# accra_a0_B.net
KiCad netlist of a schematic drawn in EAGLE
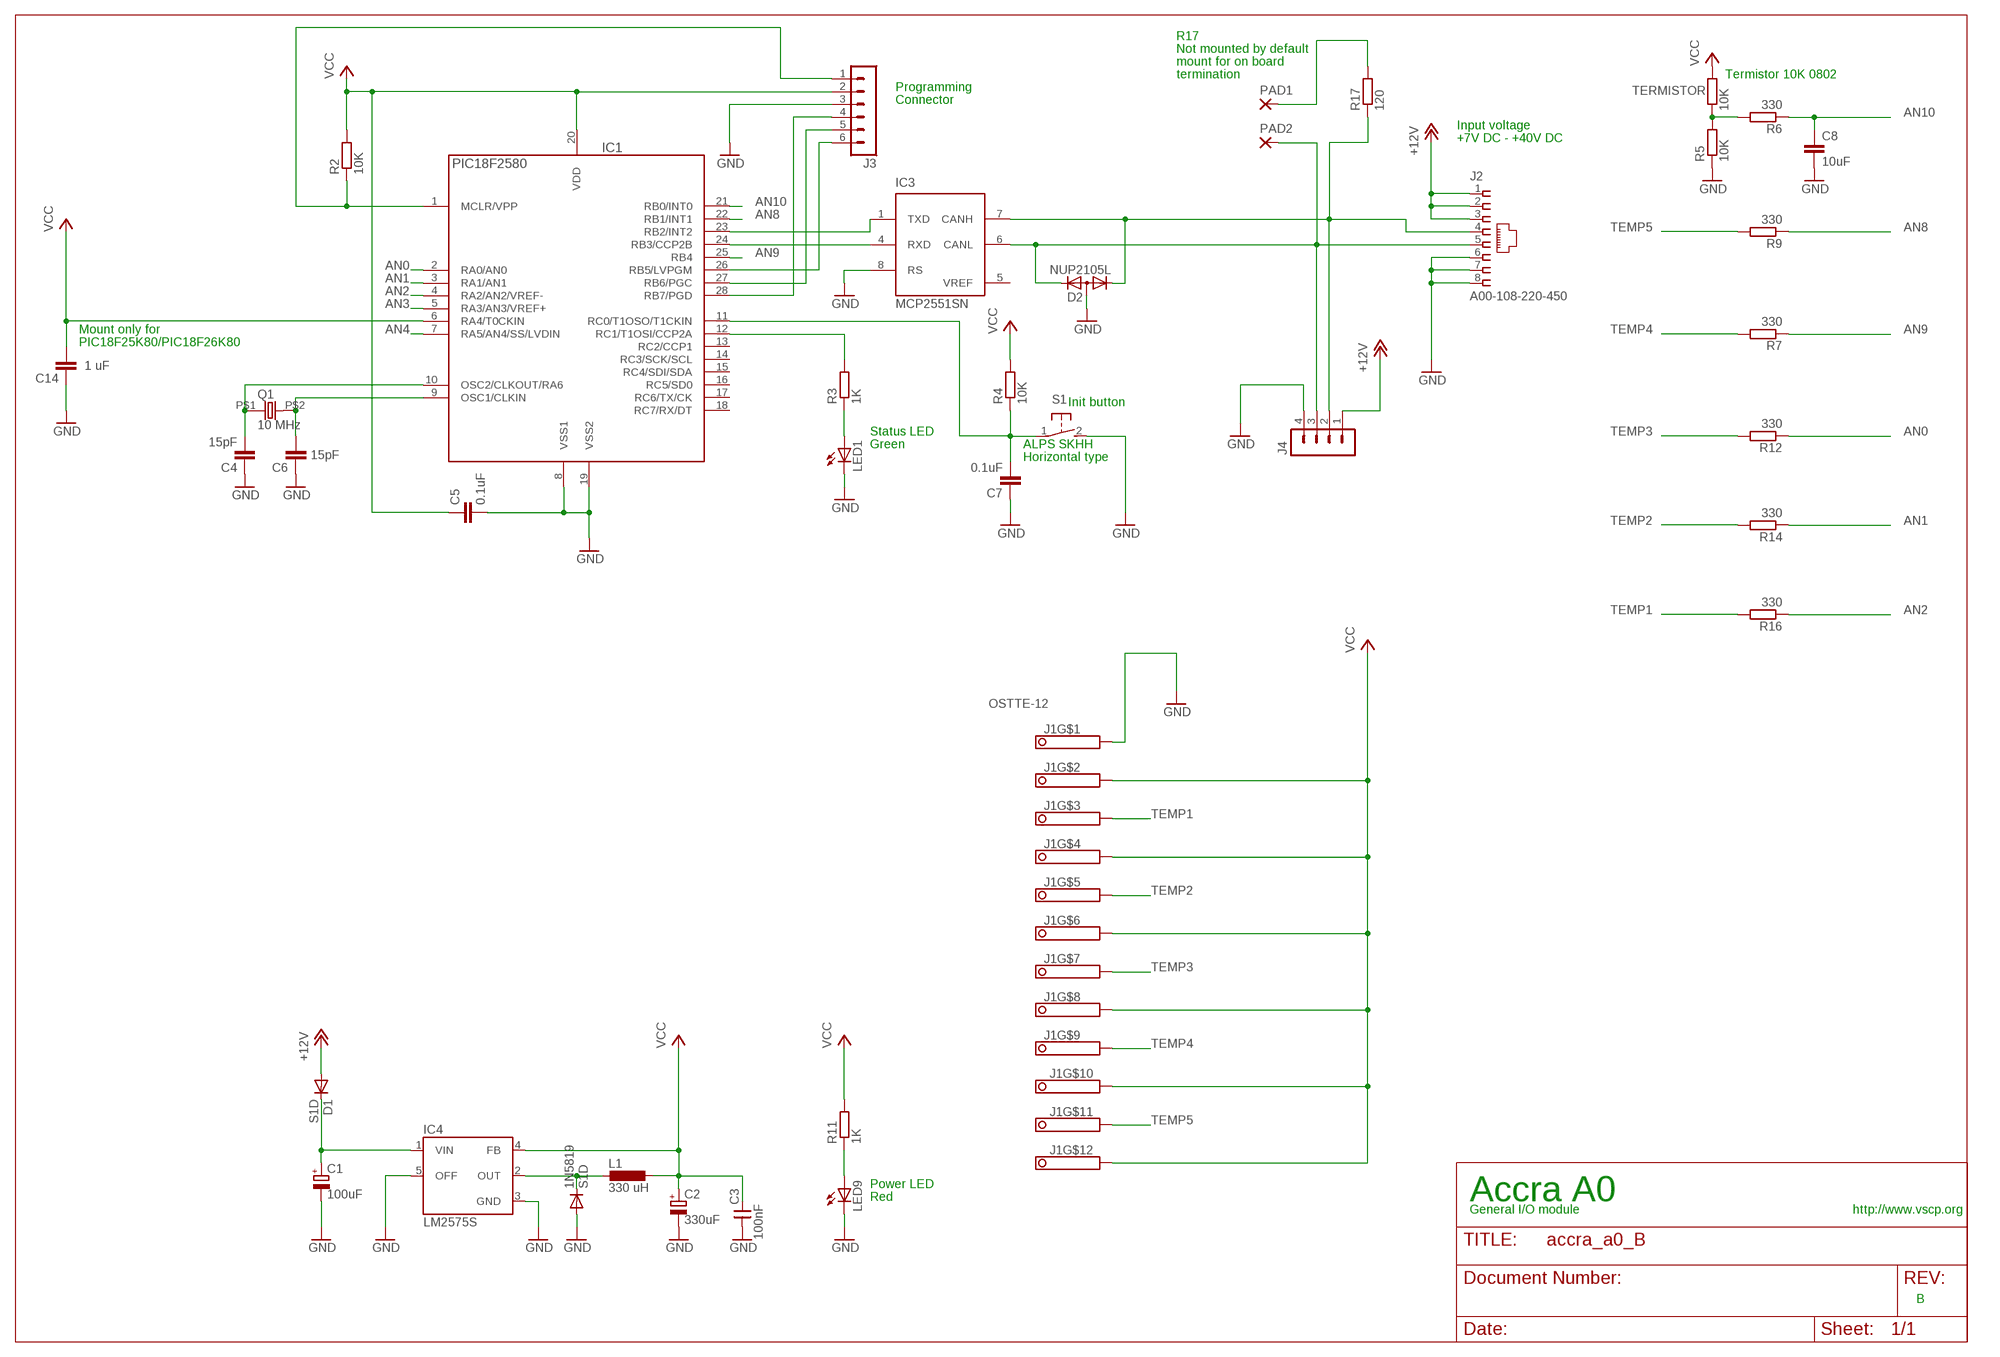
[diagram p0: schematic, sheet 1]

(export (version "E")
  (design (tool "Eeschema 10.0.6"))
  (components
    (comp (ref "1N5819")
      (value "S1D")
      (footprint "eagle-import:SOD123")
      (libsource (lib "eagle-import") (part "DIODE-SOD123"))
    )
    (comp (ref "C1")
      (value "100uF")
      (footprint "eagle-import:PANASONIC_D")
      (libsource (lib "eagle-import") (part "CPOL-EUD"))
    )
    (comp (ref "C2")
      (value "330uF")
      (footprint "eagle-import:PANASONIC_D")
      (libsource (lib "eagle-import") (part "CPOL-EUD"))
    )
    (comp (ref "C3")
      (value "100nF")
      (footprint "eagle-import:0805")
      (libsource (lib "eagle-import") (part "CNP-0805"))
    )
    (comp (ref "C4")
      (value "15pF")
      (footprint "eagle-import:C0805")
      (libsource (lib "eagle-import") (part "C-EUC0805"))
    )
    (comp (ref "C5")
      (value "0.1uF")
      (footprint "eagle-import:C0805")
      (libsource (lib "eagle-import") (part "C-EUC0805"))
    )
    (comp (ref "C6")
      (value "15pF")
      (footprint "eagle-import:C0805")
      (libsource (lib "eagle-import") (part "C-EUC0805"))
    )
    (comp (ref "C7")
      (value "0.1uF")
      (footprint "eagle-import:C0805")
      (libsource (lib "eagle-import") (part "C-EUC0805"))
    )
    (comp (ref "C8")
      (value "10uF")
      (footprint "eagle-import:C0805")
      (libsource (lib "eagle-import") (part "C-EUC0805"))
    )
    (comp (ref "C14")
      (value "1 uF")
      (footprint "eagle-import:C0805")
      (libsource (lib "eagle-import") (part "C-EUC0805"))
    )
    (comp (ref "D1")
      (value "S1D")
      (footprint "eagle-import:SOD123")
      (libsource (lib "eagle-import") (part "DIODE-SOD123"))
    )
    (comp (ref "D2")
      (value "NUP2105L")
      (footprint "eagle-import:SOT23")
      (libsource (lib "eagle-import") (part "DIODE-2CA|ACSOT23"))
    )
    (comp (ref "IC1")
      (value "PIC18F2580")
      (footprint "eagle-import:SO28")
      (libsource (lib "eagle-import") (part "PIC18F252-?I/SOL"))
    )
    (comp (ref "IC3")
      (value "MCP2551SN")
      (footprint "eagle-import:SO-08")
      (libsource (lib "eagle-import") (part "MCP2551SN"))
    )
    (comp (ref "IC4")
      (value "LM2575S")
      (footprint "eagle-import:TO263-5")
      (libsource (lib "eagle-import") (part "LM2575S"))
    )
    (comp (ref "J1")
      (value "OSTTE-12")
      (footprint "eagle-import:PINHEAD-12")
      (libsource (lib "eagle-import") (part "OSTTE-12"))
    )
    (comp (ref "J2")
      (value "A00-108-220-450")
      (footprint "eagle-import:RJ-45")
      (libsource (lib "eagle-import") (part "A00-108-220-450"))
    )
    (comp (ref "J3")
      (value "MA06-1")
      (footprint "eagle-import:MA06-1")
      (libsource (lib "eagle-import") (part "MA06-1"))
    )
    (comp (ref "J4")
      (value "MA04-1")
      (footprint "eagle-import:MA04-1")
      (libsource (lib "eagle-import") (part "MA04-1"))
    )
    (comp (ref "L1")
      (value "330 uH")
      (footprint "eagle-import:DO3316P")
      (libsource (lib "eagle-import") (part "DO3316P"))
    )
    (comp (ref "LED1")
      (value "LEDCHIP-LED0805")
      (footprint "eagle-import:CHIP-LED0805")
      (libsource (lib "eagle-import") (part "LEDCHIP-LED0805"))
    )
    (comp (ref "LED9")
      (value "LEDCHIP-LED0805")
      (footprint "eagle-import:CHIP-LED0805")
      (libsource (lib "eagle-import") (part "LEDCHIP-LED0805"))
    )
    (comp (ref "PAD1")
      (value "1,6/0,8")
      (footprint "eagle-import:1,6_0,8")
      (libsource (lib "eagle-import") (part "1,6/0,8"))
    )
    (comp (ref "PAD2")
      (value "1,6/0,8")
      (footprint "eagle-import:1,6_0,8")
      (libsource (lib "eagle-import") (part "1,6/0,8"))
    )
    (comp (ref "Q1")
      (value "10 MHz")
      (footprint "eagle-import:9C")
      (libsource (lib "eagle-import") (part "HC-49S"))
    )
    (comp (ref "R2")
      (value "10K")
      (footprint "eagle-import:R0805")
      (libsource (lib "eagle-import") (part "R-EU_R0805"))
    )
    (comp (ref "R3")
      (value "1K")
      (footprint "eagle-import:R0805")
      (libsource (lib "eagle-import") (part "R-EU_R0805"))
    )
    (comp (ref "R4")
      (value "10K")
      (footprint "eagle-import:R0805")
      (libsource (lib "eagle-import") (part "R-EU_R0805"))
    )
    (comp (ref "R5")
      (value "10K")
      (footprint "eagle-import:R0805")
      (libsource (lib "eagle-import") (part "R-EU_R0805"))
    )
    (comp (ref "R6")
      (value "330")
      (footprint "eagle-import:R0805")
      (libsource (lib "eagle-import") (part "R-EU_R0805"))
    )
    (comp (ref "R7")
      (value "330")
      (footprint "eagle-import:R0805")
      (libsource (lib "eagle-import") (part "R-EU_R0805"))
    )
    (comp (ref "R9")
      (value "330")
      (footprint "eagle-import:R0805")
      (libsource (lib "eagle-import") (part "R-EU_R0805"))
    )
    (comp (ref "R11")
      (value "1K")
      (footprint "eagle-import:R0805")
      (libsource (lib "eagle-import") (part "R-EU_R0805"))
    )
    (comp (ref "R12")
      (value "330")
      (footprint "eagle-import:R0805")
      (libsource (lib "eagle-import") (part "R-EU_R0805"))
    )
    (comp (ref "R14")
      (value "330")
      (footprint "eagle-import:R0805")
      (libsource (lib "eagle-import") (part "R-EU_R0805"))
    )
    (comp (ref "R16")
      (value "330")
      (footprint "eagle-import:R0805")
      (libsource (lib "eagle-import") (part "R-EU_R0805"))
    )
    (comp (ref "R17")
      (value "120")
      (footprint "eagle-import:R0805")
      (libsource (lib "eagle-import") (part "R-EU_R0805"))
    )
    (comp (ref "S1")
      (value "31-XX")
      (footprint "eagle-import:B3F-31XX")
      (fields (field (name "MPN") "B3F-3100"))
      (libsource (lib "eagle-import") (part "31-XX"))
    )
    (comp (ref "TERMISTOR")
      (value "10K")
      (footprint "eagle-import:R0805")
      (libsource (lib "eagle-import") (part "R-EU_R0805"))
    )
  )
  (nets
    (net (code "1") (name "+12V") (class "Default")
      (node (ref "D1") (pin "A") (pinfunction "A_A") (pintype "passive"))
      (node (ref "J2") (pin "1") (pinfunction "1_1") (pintype "passive"))
      (node (ref "J2") (pin "2") (pinfunction "2_2") (pintype "passive"))
      (node (ref "J2") (pin "3") (pinfunction "3_3") (pintype "passive"))
      (node (ref "J4") (pin "1") (pinfunction "1_1") (pintype "passive"))
    )
    (net (code "2") (name "/AN0") (class "Default")
      (node (ref "IC1") (pin "2") (pinfunction "RA0/AN0_2") (pintype "bidirectional"))
      (node (ref "R12") (pin "1") (pinfunction "1_1") (pintype "passive"))
    )
    (net (code "3") (name "/AN1") (class "Default")
      (node (ref "IC1") (pin "3") (pinfunction "RA1/AN1_3") (pintype "bidirectional"))
      (node (ref "R14") (pin "1") (pinfunction "1_1") (pintype "passive"))
    )
    (net (code "4") (name "/AN2") (class "Default")
      (node (ref "IC1") (pin "4") (pinfunction "RA2/AN2/VREF-_4") (pintype "bidirectional"))
      (node (ref "R16") (pin "1") (pinfunction "1_1") (pintype "passive"))
    )
    (net (code "5") (name "/AN3") (class "Default")
      (node (ref "IC1") (pin "5") (pinfunction "RA3/AN3/VREF+_5") (pintype "bidirectional"))
    )
    (net (code "6") (name "/AN4") (class "Default")
      (node (ref "IC1") (pin "7") (pinfunction "RA5/AN4/SS/LVDIN_7") (pintype "bidirectional"))
    )
    (net (code "7") (name "/AN8") (class "Default")
      (node (ref "IC1") (pin "22") (pinfunction "RB1/INT1_22") (pintype "bidirectional"))
      (node (ref "R9") (pin "1") (pinfunction "1_1") (pintype "passive"))
    )
    (net (code "8") (name "/AN9") (class "Default")
      (node (ref "IC1") (pin "25") (pinfunction "RB4_25") (pintype "bidirectional"))
      (node (ref "R7") (pin "1") (pinfunction "1_1") (pintype "passive"))
    )
    (net (code "9") (name "/AN10") (class "Default")
      (node (ref "C8") (pin "1") (pinfunction "1_1") (pintype "passive"))
      (node (ref "IC1") (pin "21") (pinfunction "RB0/INT0_21") (pintype "bidirectional"))
      (node (ref "R6") (pin "1") (pinfunction "1_1") (pintype "passive"))
    )
    (net (code "10") (name "/TEMP1") (class "Default")
      (node (ref "J1") (pin "3") (pinfunction "K_3") (pintype "passive"))
      (node (ref "R16") (pin "2") (pinfunction "2_2") (pintype "passive"))
    )
    (net (code "11") (name "/TEMP2") (class "Default")
      (node (ref "J1") (pin "5") (pinfunction "K_5") (pintype "passive"))
      (node (ref "R14") (pin "2") (pinfunction "2_2") (pintype "passive"))
    )
    (net (code "12") (name "/TEMP3") (class "Default")
      (node (ref "J1") (pin "7") (pinfunction "K_7") (pintype "passive"))
      (node (ref "R12") (pin "2") (pinfunction "2_2") (pintype "passive"))
    )
    (net (code "13") (name "/TEMP4") (class "Default")
      (node (ref "J1") (pin "9") (pinfunction "K_9") (pintype "passive"))
      (node (ref "R7") (pin "2") (pinfunction "2_2") (pintype "passive"))
    )
    (net (code "14") (name "/TEMP5") (class "Default")
      (node (ref "J1") (pin "11") (pinfunction "K_11") (pintype "passive"))
      (node (ref "R9") (pin "2") (pinfunction "2_2") (pintype "passive"))
    )
    (net (code "15") (name "/VREF") (class "Default")
      (node (ref "IC3") (pin "5") (pinfunction "VREF_5") (pintype "power_in"))
    )
    (net (code "16") (name "GND") (class "Default")
      (node (ref "1N5819") (pin "A") (pinfunction "A_A") (pintype "passive"))
      (node (ref "C1") (pin "-") (pinfunction "-_-") (pintype "passive"))
      (node (ref "C14") (pin "1") (pinfunction "1_1") (pintype "passive"))
      (node (ref "C2") (pin "-") (pinfunction "-_-") (pintype "passive"))
      (node (ref "C3") (pin "1") (pinfunction "1_1") (pintype "passive"))
      (node (ref "C4") (pin "1") (pinfunction "1_1") (pintype "passive"))
      (node (ref "C5") (pin "2") (pinfunction "2_2") (pintype "passive"))
      (node (ref "C6") (pin "1") (pinfunction "1_1") (pintype "passive"))
      (node (ref "C7") (pin "1") (pinfunction "1_1") (pintype "passive"))
      (node (ref "C8") (pin "2") (pinfunction "2_2") (pintype "passive"))
      (node (ref "D2") (pin "3") (pinfunction "A_3") (pintype "passive"))
      (node (ref "IC1") (pin "19") (pinfunction "VSS2_19") (pintype "power_in"))
      (node (ref "IC1") (pin "8") (pinfunction "VSS1_8") (pintype "power_in"))
      (node (ref "IC3") (pin "8") (pinfunction "RS_8") (pintype "input"))
      (node (ref "IC4") (pin "3") (pinfunction "GND_3") (pintype "power_in"))
      (node (ref "IC4") (pin "5") (pinfunction "OFF_5") (pintype "input"))
      (node (ref "J1") (pin "1") (pinfunction "K_1") (pintype "passive"))
      (node (ref "J2") (pin "6") (pinfunction "6_6") (pintype "passive"))
      (node (ref "J2") (pin "7") (pinfunction "7_7") (pintype "passive"))
      (node (ref "J2") (pin "8") (pinfunction "8_8") (pintype "passive"))
      (node (ref "J3") (pin "3") (pinfunction "3_3") (pintype "passive"))
      (node (ref "J4") (pin "4") (pinfunction "4_4") (pintype "passive"))
      (node (ref "LED1") (pin "C") (pinfunction "C_C") (pintype "passive"))
      (node (ref "LED9") (pin "C") (pinfunction "C_C") (pintype "passive"))
      (node (ref "R5") (pin "1") (pinfunction "1_1") (pintype "passive"))
      (node (ref "S1") (pin "2") (pinfunction "S_2") (pintype "passive"))
    )
    (net (code "17") (name "Net-(D2-K1)") (class "Default")
      (node (ref "D2") (pin "1") (pinfunction "K1_1") (pintype "passive"))
      (node (ref "IC3") (pin "7") (pinfunction "CANH_7") (pintype "bidirectional"))
      (node (ref "J2") (pin "4") (pinfunction "4_4") (pintype "passive"))
      (node (ref "J4") (pin "2") (pinfunction "2_2") (pintype "passive"))
      (node (ref "R17") (pin "1") (pinfunction "1_1") (pintype "passive"))
    )
    (net (code "18") (name "Net-(D2-K2)") (class "Default")
      (node (ref "D2") (pin "2") (pinfunction "K2_2") (pintype "passive"))
      (node (ref "IC3") (pin "6") (pinfunction "CANL_6") (pintype "bidirectional"))
      (node (ref "J2") (pin "5") (pinfunction "5_5") (pintype "passive"))
      (node (ref "J4") (pin "3") (pinfunction "3_3") (pintype "passive"))
      (node (ref "PAD2") (pin "1") (pinfunction "P_1") (pintype "passive"))
    )
    (net (code "19") (name "Net-(IC1-MCLR{slash}VPP)") (class "Default")
      (node (ref "IC1") (pin "1") (pinfunction "MCLR/VPP_1") (pintype "input"))
      (node (ref "J3") (pin "1") (pinfunction "1_1") (pintype "passive"))
      (node (ref "R2") (pin "1") (pinfunction "1_1") (pintype "passive"))
    )
    (net (code "20") (name "Net-(IC1-OSC1{slash}CLKIN)") (class "Default")
      (node (ref "C6") (pin "2") (pinfunction "2_2") (pintype "passive"))
      (node (ref "IC1") (pin "9") (pinfunction "OSC1/CLKIN_9") (pintype "input"))
      (node (ref "Q1") (pin "P$2") (pinfunction "2_P$2") (pintype "passive"))
    )
    (net (code "21") (name "Net-(IC1-OSC2{slash}CLKOUT{slash}RA6)") (class "Default")
      (node (ref "C4") (pin "2") (pinfunction "2_2") (pintype "passive"))
      (node (ref "IC1") (pin "10") (pinfunction "OSC2/CLKOUT/RA6_10") (pintype "output"))
      (node (ref "Q1") (pin "P$1") (pinfunction "1_P$1") (pintype "passive"))
    )
    (net (code "22") (name "Net-(IC1-RB2{slash}INT2)") (class "Default")
      (node (ref "IC1") (pin "23") (pinfunction "RB2/INT2_23") (pintype "bidirectional"))
      (node (ref "IC3") (pin "1") (pinfunction "TXD_1") (pintype "input"))
    )
    (net (code "23") (name "Net-(IC1-RB3{slash}CCP2B)") (class "Default")
      (node (ref "IC1") (pin "24") (pinfunction "RB3/CCP2B_24") (pintype "bidirectional"))
      (node (ref "IC3") (pin "4") (pinfunction "RXD_4") (pintype "output"))
    )
    (net (code "24") (name "Net-(IC1-RB5{slash}LVPGM)") (class "Default")
      (node (ref "IC1") (pin "26") (pinfunction "RB5/LVPGM_26") (pintype "bidirectional"))
      (node (ref "J3") (pin "6") (pinfunction "6_6") (pintype "passive"))
    )
    (net (code "25") (name "Net-(IC1-RB6{slash}PGC)") (class "Default")
      (node (ref "IC1") (pin "27") (pinfunction "RB6/PGC_27") (pintype "bidirectional"))
      (node (ref "J3") (pin "5") (pinfunction "5_5") (pintype "passive"))
    )
    (net (code "26") (name "Net-(IC1-RB7{slash}PGD)") (class "Default")
      (node (ref "IC1") (pin "28") (pinfunction "RB7/PGD_28") (pintype "bidirectional"))
      (node (ref "J3") (pin "4") (pinfunction "4_4") (pintype "passive"))
    )
    (net (code "27") (name "Net-(IC1-RC0{slash}T1OSO{slash}T1CKIN)") (class "Default")
      (node (ref "C7") (pin "2") (pinfunction "2_2") (pintype "passive"))
      (node (ref "IC1") (pin "11") (pinfunction "RC0/T1OSO/T1CKIN_11") (pintype "bidirectional"))
      (node (ref "R4") (pin "1") (pinfunction "1_1") (pintype "passive"))
      (node (ref "S1") (pin "1") (pinfunction "P_1") (pintype "passive"))
    )
    (net (code "28") (name "Net-(IC1-RC1{slash}T1OSI{slash}CCP2A)") (class "Default")
      (node (ref "IC1") (pin "12") (pinfunction "RC1/T1OSI/CCP2A_12") (pintype "bidirectional"))
      (node (ref "R3") (pin "2") (pinfunction "2_2") (pintype "passive"))
    )
    (net (code "29") (name "Net-(IC4-OUT)") (class "Default")
      (node (ref "1N5819") (pin "C") (pinfunction "C_C") (pintype "passive"))
      (node (ref "IC4") (pin "2") (pinfunction "OUT_2") (pintype "output"))
      (node (ref "L1") (pin "1") (pinfunction "1_1") (pintype "passive"))
    )
    (net (code "30") (name "Net-(IC4-VIN)") (class "Default")
      (node (ref "C1") (pin "+") (pinfunction "+_+") (pintype "passive"))
      (node (ref "D1") (pin "C") (pinfunction "C_C") (pintype "passive"))
      (node (ref "IC4") (pin "1") (pinfunction "VIN_1") (pintype "power_in"))
    )
    (net (code "31") (name "Net-(LED1-PadA)") (class "Default")
      (node (ref "LED1") (pin "A") (pinfunction "A_A") (pintype "passive"))
      (node (ref "R3") (pin "1") (pinfunction "1_1") (pintype "passive"))
    )
    (net (code "32") (name "Net-(LED9-PadA)") (class "Default")
      (node (ref "LED9") (pin "A") (pinfunction "A_A") (pintype "passive"))
      (node (ref "R11") (pin "1") (pinfunction "1_1") (pintype "passive"))
    )
    (net (code "33") (name "Net-(PAD1-P)") (class "Default")
      (node (ref "PAD1") (pin "1") (pinfunction "P_1") (pintype "passive"))
      (node (ref "R17") (pin "2") (pinfunction "2_2") (pintype "passive"))
    )
    (net (code "34") (name "Net-(R5-Pad2)") (class "Default")
      (node (ref "R5") (pin "2") (pinfunction "2_2") (pintype "passive"))
      (node (ref "R6") (pin "2") (pinfunction "2_2") (pintype "passive"))
      (node (ref "TERMISTOR") (pin "1") (pinfunction "1_1") (pintype "passive"))
    )
    (net (code "35") (name "VCC") (class "Default")
      (node (ref "C14") (pin "2") (pinfunction "2_2") (pintype "passive"))
      (node (ref "C2") (pin "+") (pinfunction "+_+") (pintype "passive"))
      (node (ref "C3") (pin "2") (pinfunction "2_2") (pintype "passive"))
      (node (ref "C5") (pin "1") (pinfunction "1_1") (pintype "passive"))
      (node (ref "IC1") (pin "20") (pinfunction "VDD_20") (pintype "power_in"))
      (node (ref "IC1") (pin "6") (pinfunction "RA4/T0CKIN_6") (pintype "open_collector"))
      (node (ref "IC4") (pin "4") (pinfunction "FB_4") (pintype "input"))
      (node (ref "J1") (pin "10") (pinfunction "K_10") (pintype "passive"))
      (node (ref "J1") (pin "12") (pinfunction "K_12") (pintype "passive"))
      (node (ref "J1") (pin "2") (pinfunction "K_2") (pintype "passive"))
      (node (ref "J1") (pin "4") (pinfunction "K_4") (pintype "passive"))
      (node (ref "J1") (pin "6") (pinfunction "K_6") (pintype "passive"))
      (node (ref "J1") (pin "8") (pinfunction "K_8") (pintype "passive"))
      (node (ref "J3") (pin "2") (pinfunction "2_2") (pintype "passive"))
      (node (ref "L1") (pin "2") (pinfunction "2_2") (pintype "passive"))
      (node (ref "R11") (pin "2") (pinfunction "2_2") (pintype "passive"))
      (node (ref "R2") (pin "2") (pinfunction "2_2") (pintype "passive"))
      (node (ref "R4") (pin "2") (pinfunction "2_2") (pintype "passive"))
      (node (ref "TERMISTOR") (pin "2") (pinfunction "2_2") (pintype "passive"))
    )
    (net (code "36") (name "unconnected-(IC1-RC2{slash}CCP1-Pad13)") (class "Default")
      (node (ref "IC1") (pin "13") (pinfunction "RC2/CCP1_13") (pintype "bidirectional"))
    )
    (net (code "37") (name "unconnected-(IC1-RC3{slash}SCK{slash}SCL-Pad14)") (class "Default")
      (node (ref "IC1") (pin "14") (pinfunction "RC3/SCK/SCL_14") (pintype "bidirectional"))
    )
    (net (code "38") (name "unconnected-(IC1-RC4{slash}SDI{slash}SDA-Pad15)") (class "Default")
      (node (ref "IC1") (pin "15") (pinfunction "RC4/SDI/SDA_15") (pintype "bidirectional"))
    )
    (net (code "39") (name "unconnected-(IC1-RC5{slash}SD0-Pad16)") (class "Default")
      (node (ref "IC1") (pin "16") (pinfunction "RC5/SD0_16") (pintype "bidirectional"))
    )
    (net (code "40") (name "unconnected-(IC1-RC6{slash}TX{slash}CK-Pad17)") (class "Default")
      (node (ref "IC1") (pin "17") (pinfunction "RC6/TX/CK_17") (pintype "bidirectional"))
    )
    (net (code "41") (name "unconnected-(IC1-RC7{slash}RX{slash}DT-Pad18)") (class "Default")
      (node (ref "IC1") (pin "18") (pinfunction "RC7/RX/DT_18") (pintype "bidirectional"))
    )
  )
)
